# SCH_Group-50_Final_2026-01-02.net
KiCad netlist of a schematic drawn in EasyEDA
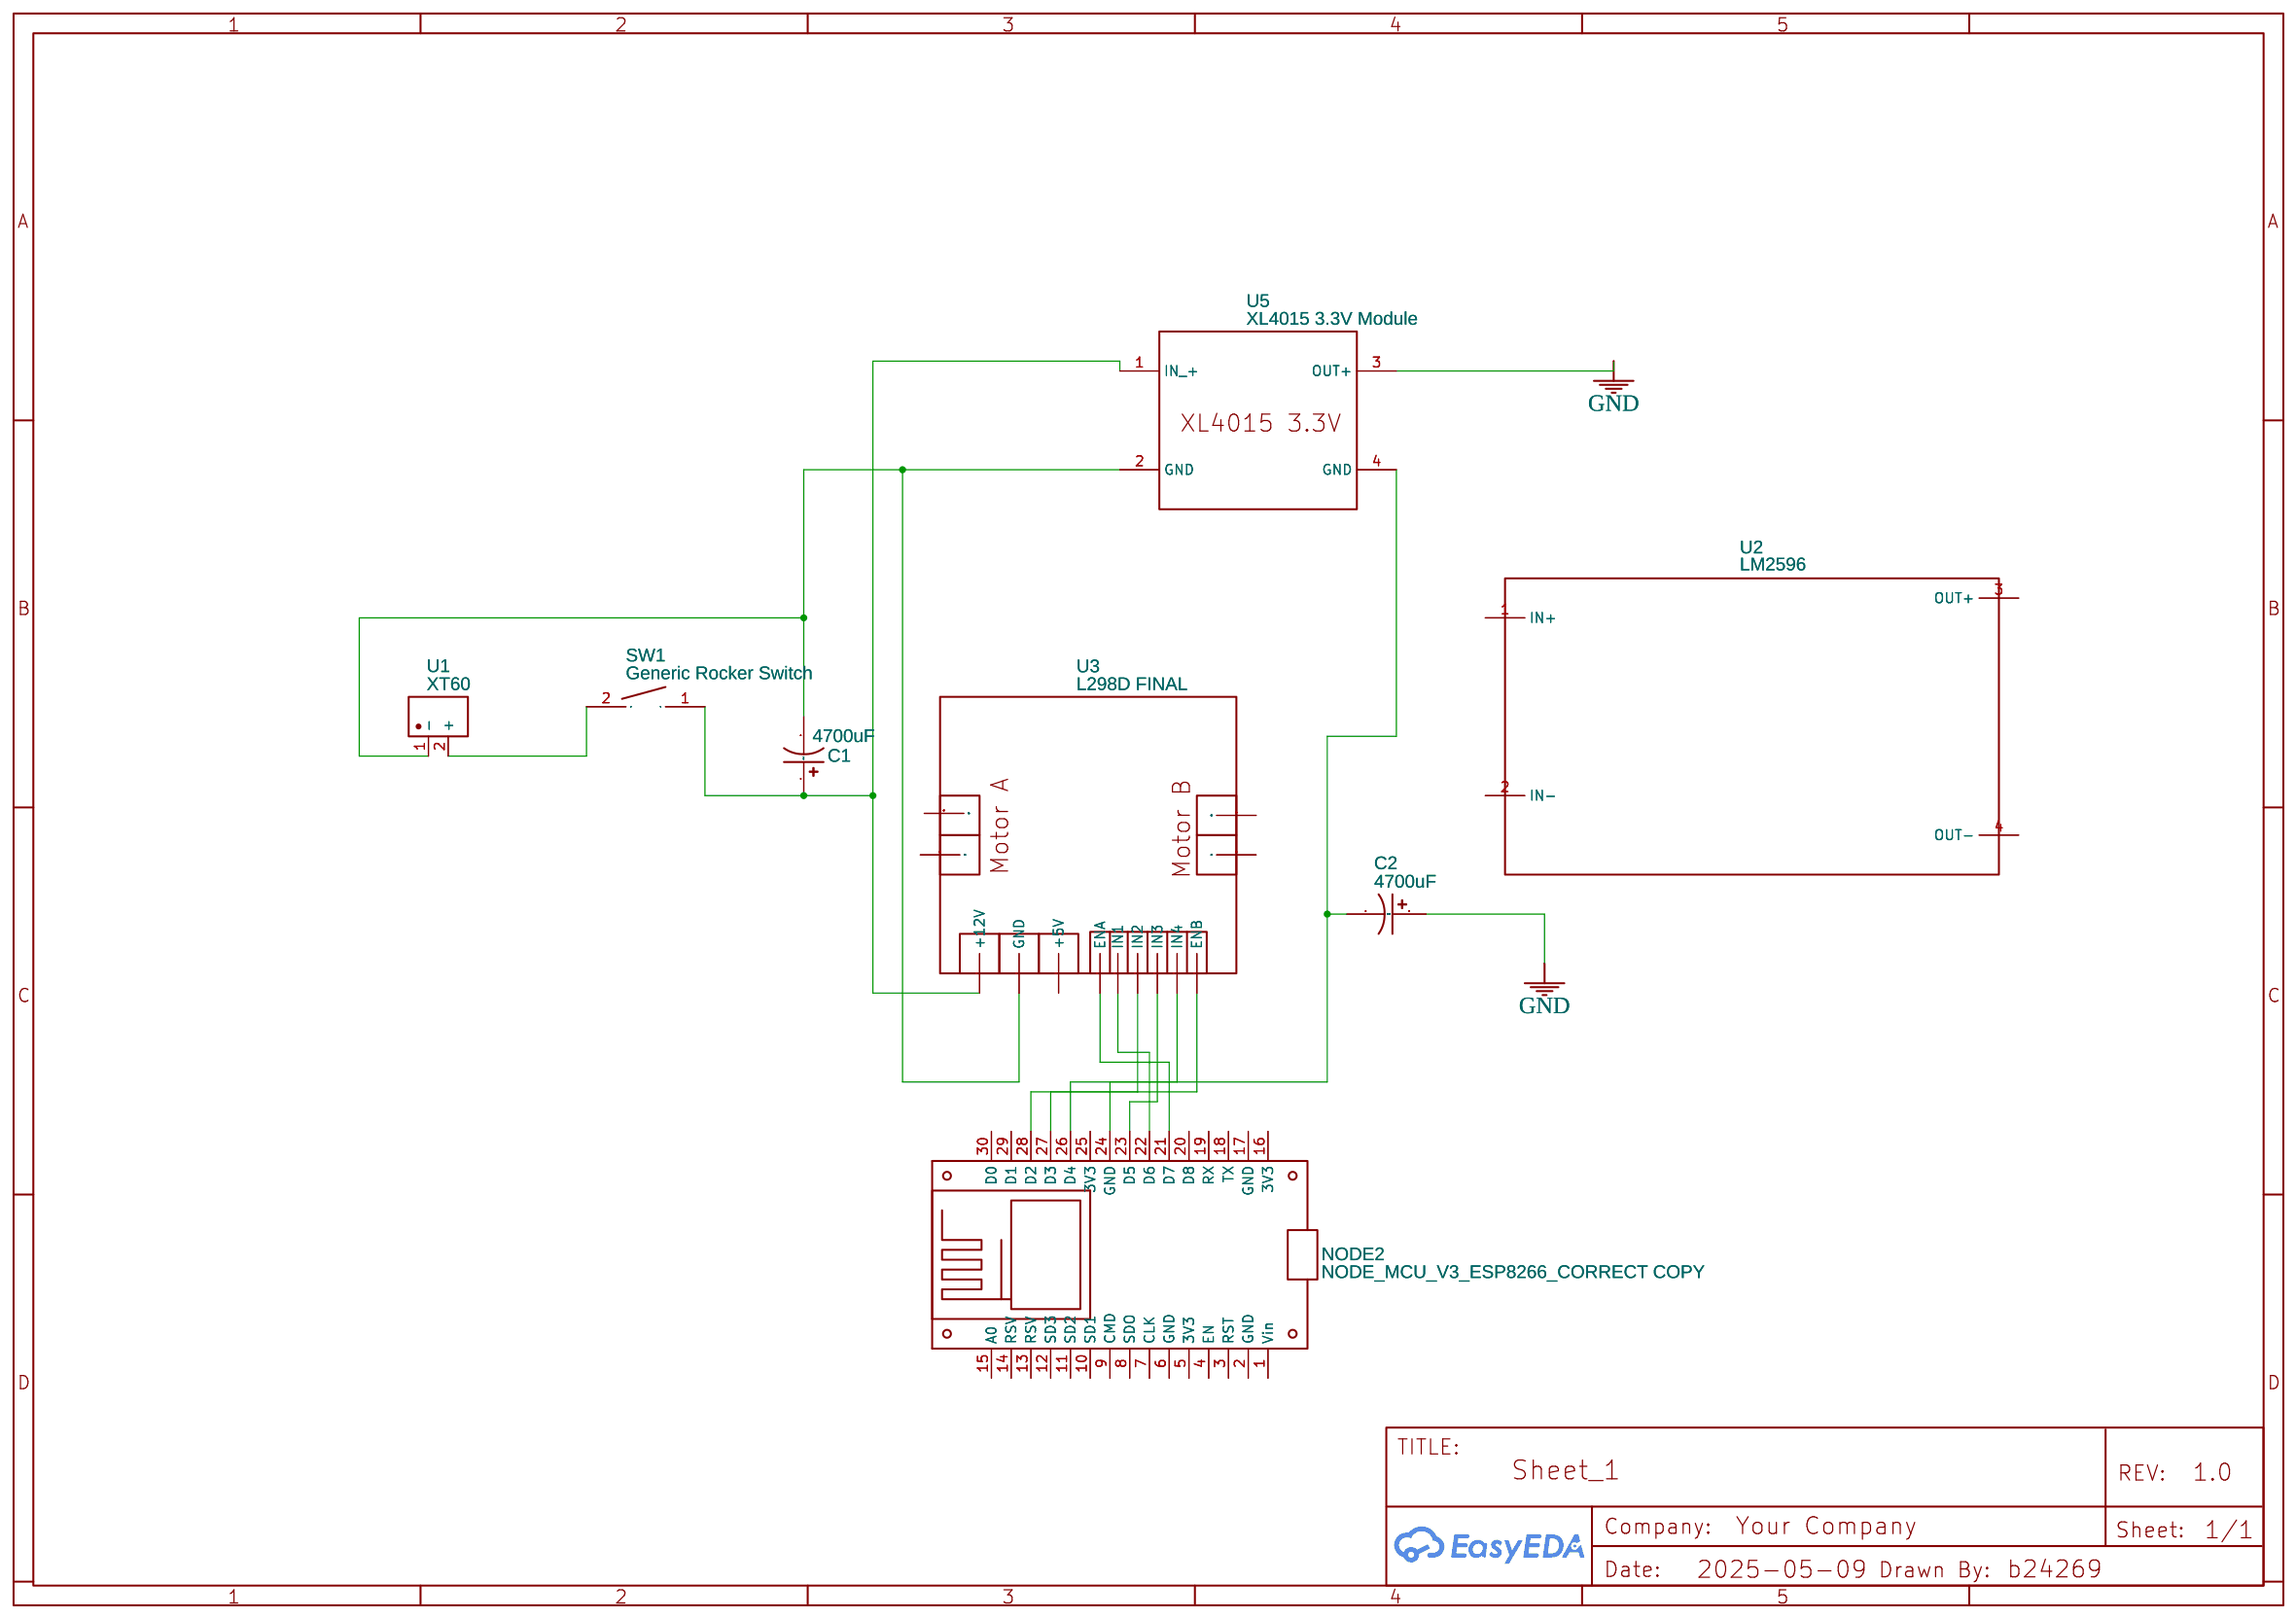
[diagram p0: schematic sheet]

(export (version "E")
  (design (tool "Eeschema 10.0.6"))
  (components
    (comp (ref "C1") (value "4700uF") (libsource (lib "") (part "4700UF 25V 16X25")))
    (comp (ref "C2") (value "4700uF") (libsource (lib "") (part "4700UF 25V 16X25_1")))
    (comp (ref "NODE2")
      (value "NODE_MCU_V3_ESP8266_CORRECT COPY")
      (libsource (lib "") (part "NODE_MCU_V3_ESP8266_CORRECT COPY"))
    )
    (comp (ref "SW1")
      (value "Generic Rocker Switch")
      (fields (field (name "Manufacturer Part") "R1966FBLKWHTEF") (field (name "Manufacturer") "E-Switch"))
      (libsource (lib "") (part "Generic Rocker Switch"))
    )
    (comp (ref "U1")
      (value "XT60")
      (fields (field (name "Manufacturer") "AMASS(艾迈斯)"))
      (libsource (lib "") (part "XT60"))
    )
    (comp (ref "U2") (value "LM2596") (libsource (lib "") (part "LM2596")))
    (comp (ref "U3") (value "L298D FINAL") (libsource (lib "") (part "L298D FINAL")))
    (comp (ref "U5") (value "XL4015 3.3V Module") (libsource (lib "") (part "XL4015 3.3V Module")))
  )
  (nets
    (net (code "1") (name "GND") (class "Default")
      (node (ref "C2") (pin "1") (pinfunction "1_1") (pintype "unspecified"))
      (node (ref "U5") (pin "3") (pinfunction "OUT+_3") (pintype "unspecified"))
    )
    (net (code "2") (name "Net-(C2-Pad2)") (class "Default")
      (node (ref "C2") (pin "2") (pinfunction "2_2") (pintype "unspecified"))
      (node (ref "NODE2") (pin "24") (pinfunction "GND_24") (pintype "unspecified"))
      (node (ref "U5") (pin "4") (pinfunction "GND_4") (pintype "unspecified"))
    )
    (net (code "3") (name "Net-(NODE2-D2)") (class "Default")
      (node (ref "NODE2") (pin "28") (pinfunction "D2_28") (pintype "unspecified"))
      (node (ref "U3") (pin "IN2") (pinfunction "IN2_IN2") (pintype "unspecified"))
    )
    (net (code "4") (name "Net-(NODE2-D3)") (class "Default")
      (node (ref "NODE2") (pin "27") (pinfunction "D3_27") (pintype "unspecified"))
      (node (ref "U3") (pin "ENB") (pinfunction "ENB_ENB") (pintype "unspecified"))
    )
    (net (code "5") (name "Net-(NODE2-D4)") (class "Default")
      (node (ref "NODE2") (pin "26") (pinfunction "D4_26") (pintype "unspecified"))
      (node (ref "U3") (pin "IN4") (pinfunction "IN4_IN4") (pintype "unspecified"))
    )
    (net (code "6") (name "Net-(NODE2-D5)") (class "Default")
      (node (ref "NODE2") (pin "23") (pinfunction "D5_23") (pintype "unspecified"))
      (node (ref "U3") (pin "IN3") (pinfunction "IN3_IN3") (pintype "unspecified"))
    )
    (net (code "7") (name "Net-(NODE2-D6)") (class "Default")
      (node (ref "NODE2") (pin "22") (pinfunction "D6_22") (pintype "unspecified"))
      (node (ref "U3") (pin "IN1") (pinfunction "IN1_IN1") (pintype "unspecified"))
    )
    (net (code "8") (name "Net-(NODE2-D7)") (class "Default")
      (node (ref "NODE2") (pin "21") (pinfunction "D7_21") (pintype "unspecified"))
      (node (ref "U3") (pin "ENA") (pinfunction "ENA_ENA") (pintype "unspecified"))
    )
    (net (code "9") (name "Net-(U1-+)") (class "Default")
      (node (ref "SW1") (pin "2") (pinfunction "2_2") (pintype "input"))
      (node (ref "U1") (pin "2") (pinfunction "+_2") (pintype "unspecified"))
    )
    (net (code "10") (name "Net-(U1--)") (class "Default")
      (node (ref "C1") (pin "2") (pinfunction "2_2") (pintype "unspecified"))
      (node (ref "U1") (pin "1") (pinfunction "-_1") (pintype "unspecified"))
      (node (ref "U3") (pin "GND") (pinfunction "GND_GND") (pintype "unspecified"))
      (node (ref "U5") (pin "2") (pinfunction "GND_2") (pintype "unspecified"))
    )
    (net (code "11") (name "Net-(U5-IN_+)") (class "Default")
      (node (ref "C1") (pin "1") (pinfunction "1_1") (pintype "unspecified"))
      (node (ref "SW1") (pin "1") (pinfunction "1_1") (pintype "input"))
      (node (ref "U3") (pin "+12V") (pinfunction "+12V_+12V") (pintype "unspecified"))
      (node (ref "U5") (pin "1") (pinfunction "IN_+_1") (pintype "unspecified"))
    )
    (net (code "12") (name "unconnected-(NODE2-3V3-Pad5)") (class "Default")
      (node (ref "NODE2") (pin "5") (pinfunction "3V3_5") (pintype "unspecified"))
    )
    (net (code "13") (name "unconnected-(NODE2-3V3-Pad16)") (class "Default")
      (node (ref "NODE2") (pin "16") (pinfunction "3V3_16") (pintype "unspecified"))
    )
    (net (code "14") (name "unconnected-(NODE2-3V3-Pad25)") (class "Default")
      (node (ref "NODE2") (pin "25") (pinfunction "3V3_25") (pintype "unspecified"))
    )
    (net (code "15") (name "unconnected-(NODE2-A0-Pad15)") (class "Default")
      (node (ref "NODE2") (pin "15") (pinfunction "A0_15") (pintype "unspecified"))
    )
    (net (code "16") (name "unconnected-(NODE2-CLK-Pad7)") (class "Default")
      (node (ref "NODE2") (pin "7") (pinfunction "CLK_7") (pintype "unspecified"))
    )
    (net (code "17") (name "unconnected-(NODE2-CMD-Pad9)") (class "Default")
      (node (ref "NODE2") (pin "9") (pinfunction "CMD_9") (pintype "unspecified"))
    )
    (net (code "18") (name "unconnected-(NODE2-D0-Pad30)") (class "Default")
      (node (ref "NODE2") (pin "30") (pinfunction "D0_30") (pintype "unspecified"))
    )
    (net (code "19") (name "unconnected-(NODE2-D1-Pad29)") (class "Default")
      (node (ref "NODE2") (pin "29") (pinfunction "D1_29") (pintype "unspecified"))
    )
    (net (code "20") (name "unconnected-(NODE2-D8-Pad20)") (class "Default")
      (node (ref "NODE2") (pin "20") (pinfunction "D8_20") (pintype "unspecified"))
    )
    (net (code "21") (name "unconnected-(NODE2-EN-Pad4)") (class "Default")
      (node (ref "NODE2") (pin "4") (pinfunction "EN_4") (pintype "unspecified"))
    )
    (net (code "22") (name "unconnected-(NODE2-GND-Pad2)") (class "Default")
      (node (ref "NODE2") (pin "2") (pinfunction "GND_2") (pintype "unspecified"))
    )
    (net (code "23") (name "unconnected-(NODE2-GND-Pad6)") (class "Default")
      (node (ref "NODE2") (pin "6") (pinfunction "GND_6") (pintype "unspecified"))
    )
    (net (code "24") (name "unconnected-(NODE2-GND-Pad17)") (class "Default")
      (node (ref "NODE2") (pin "17") (pinfunction "GND_17") (pintype "unspecified"))
    )
    (net (code "25") (name "unconnected-(NODE2-RST-Pad3)") (class "Default")
      (node (ref "NODE2") (pin "3") (pinfunction "RST_3") (pintype "unspecified"))
    )
    (net (code "26") (name "unconnected-(NODE2-RSV-Pad13)") (class "Default")
      (node (ref "NODE2") (pin "13") (pinfunction "RSV_13") (pintype "unspecified"))
    )
    (net (code "27") (name "unconnected-(NODE2-RSV-Pad14)") (class "Default")
      (node (ref "NODE2") (pin "14") (pinfunction "RSV_14") (pintype "unspecified"))
    )
    (net (code "28") (name "unconnected-(NODE2-RX-Pad19)") (class "Default")
      (node (ref "NODE2") (pin "19") (pinfunction "RX_19") (pintype "unspecified"))
    )
    (net (code "29") (name "unconnected-(NODE2-SD1-Pad10)") (class "Default")
      (node (ref "NODE2") (pin "10") (pinfunction "SD1_10") (pintype "unspecified"))
    )
    (net (code "30") (name "unconnected-(NODE2-SD2-Pad11)") (class "Default")
      (node (ref "NODE2") (pin "11") (pinfunction "SD2_11") (pintype "unspecified"))
    )
    (net (code "31") (name "unconnected-(NODE2-SD3-Pad12)") (class "Default")
      (node (ref "NODE2") (pin "12") (pinfunction "SD3_12") (pintype "unspecified"))
    )
    (net (code "32") (name "unconnected-(NODE2-SDO-Pad8)") (class "Default")
      (node (ref "NODE2") (pin "8") (pinfunction "SDO_8") (pintype "unspecified"))
    )
    (net (code "33") (name "unconnected-(NODE2-TX-Pad18)") (class "Default")
      (node (ref "NODE2") (pin "18") (pinfunction "TX_18") (pintype "unspecified"))
    )
    (net (code "34") (name "unconnected-(NODE2-Vin-Pad1)") (class "Default")
      (node (ref "NODE2") (pin "1") (pinfunction "Vin_1") (pintype "unspecified"))
    )
    (net (code "35") (name "unconnected-(U2-IN+-Pad1)") (class "Default")
      (node (ref "U2") (pin "1") (pinfunction "IN+_1") (pintype "unspecified"))
    )
    (net (code "36") (name "unconnected-(U2-IN--Pad2)") (class "Default")
      (node (ref "U2") (pin "2") (pinfunction "IN-_2") (pintype "unspecified"))
    )
    (net (code "37") (name "unconnected-(U2-OUT+-Pad3)") (class "Default")
      (node (ref "U2") (pin "3") (pinfunction "OUT+_3") (pintype "unspecified"))
    )
    (net (code "38") (name "unconnected-(U2-OUT--Pad4)") (class "Default")
      (node (ref "U2") (pin "4") (pinfunction "OUT-_4") (pintype "unspecified"))
    )
    (net (code "39") (name "unconnected-(U3-Pad+5V)") (class "Default")
      (node (ref "U3") (pin "+5V") (pinfunction "+5V_+5V") (pintype "unspecified"))
    )
    (net (code "40") (name "unconnected-(U3-PadOUT1)") (class "Default")
      (node (ref "U3") (pin "OUT1") (pinfunction "OUT1_OUT1") (pintype "unspecified"))
    )
    (net (code "41") (name "unconnected-(U3-PadOUT2)") (class "Default")
      (node (ref "U3") (pin "OUT2") (pinfunction "OUT2_OUT2") (pintype "unspecified"))
    )
    (net (code "42") (name "unconnected-(U3-PadOUT3)") (class "Default")
      (node (ref "U3") (pin "OUT3") (pinfunction "OUT3_OUT3") (pintype "unspecified"))
    )
    (net (code "43") (name "unconnected-(U3-PadOUT4)") (class "Default")
      (node (ref "U3") (pin "OUT4") (pinfunction "OUT4_OUT4") (pintype "unspecified"))
    )
  )
)
